# AutoTunerV2.net
KiCad netlist of a schematic drawn in EAGLE
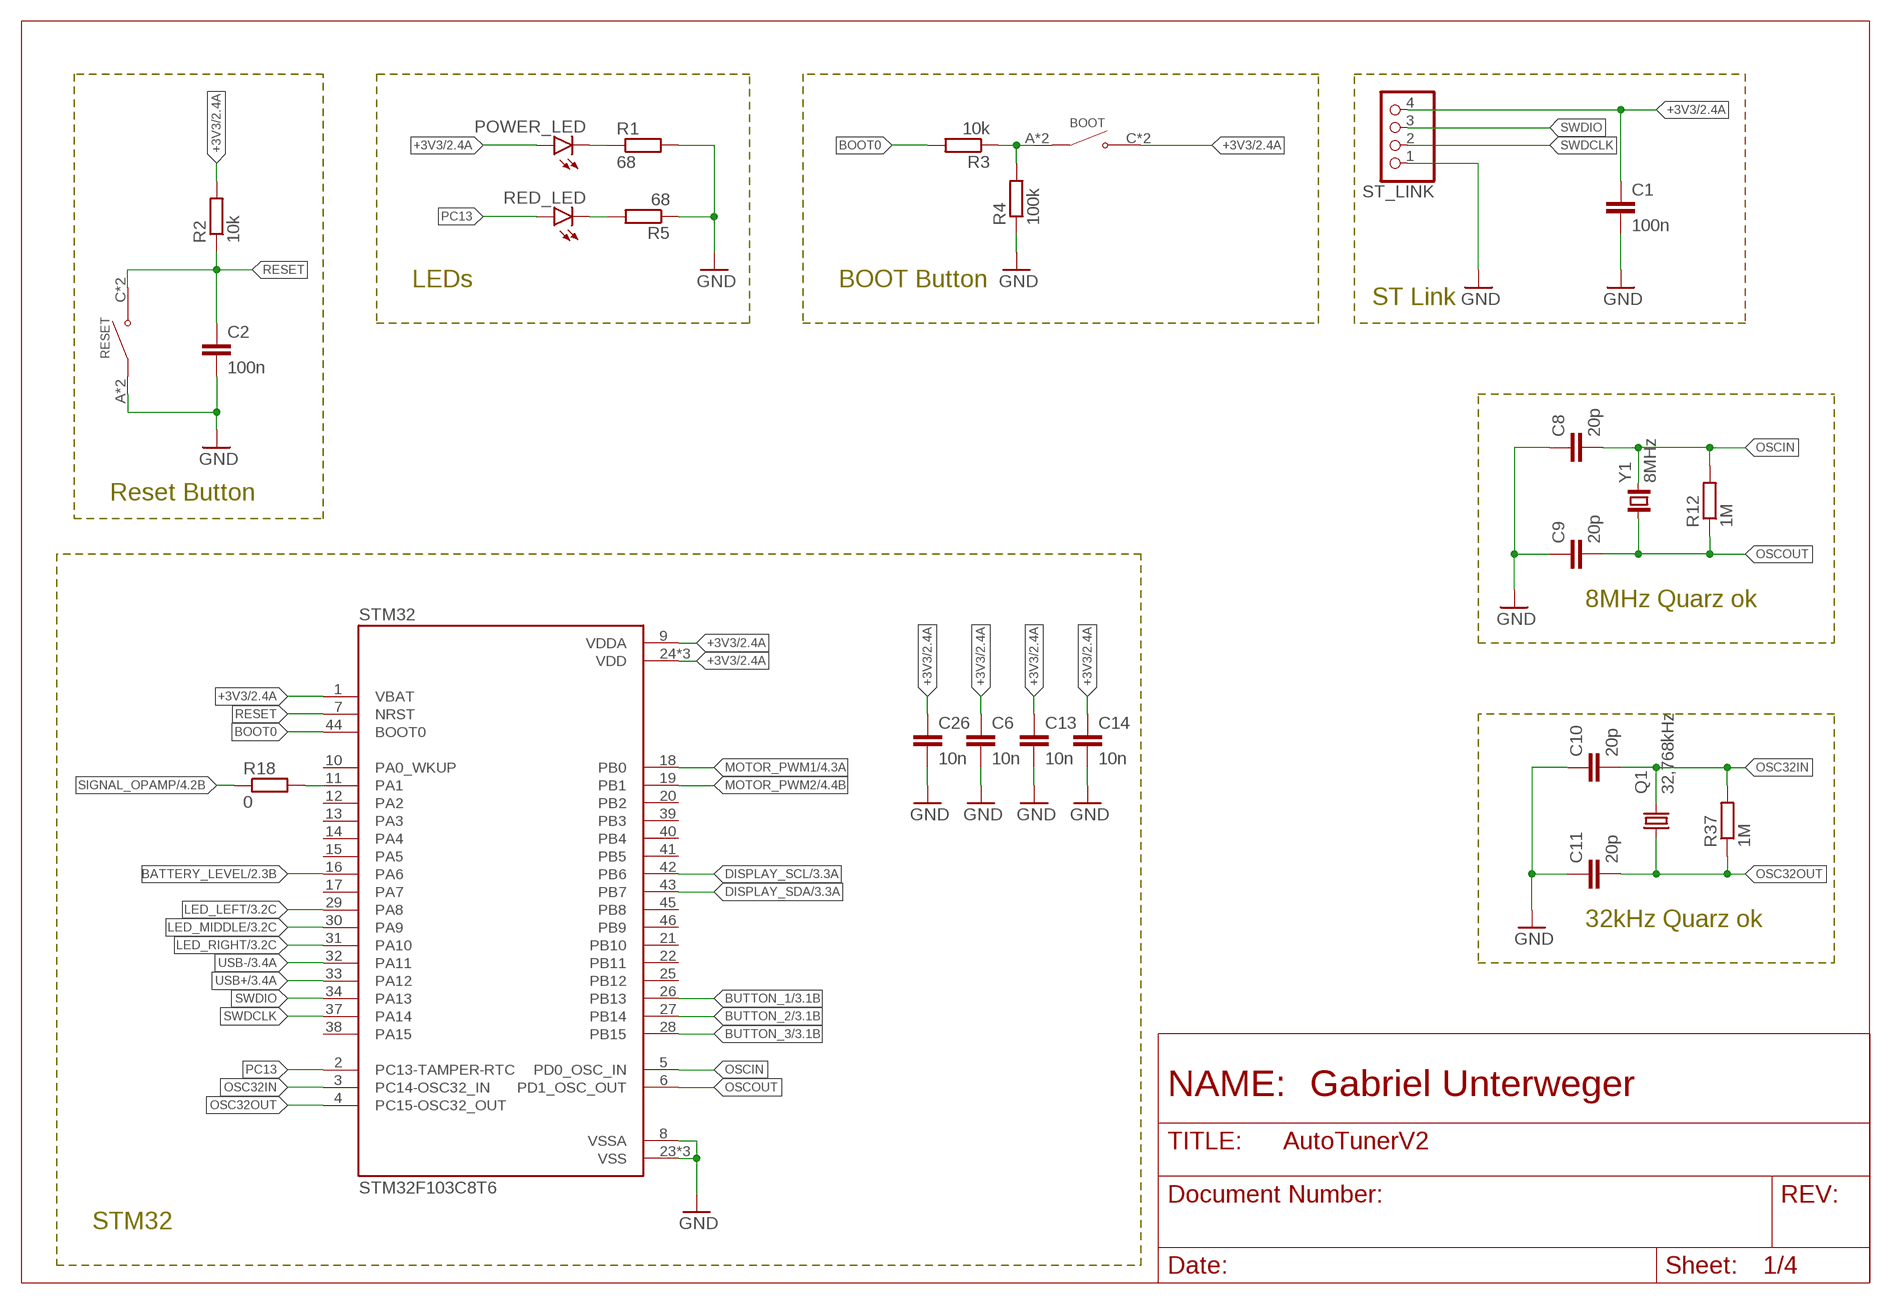
[diagram p0: schematic, sheet 1]
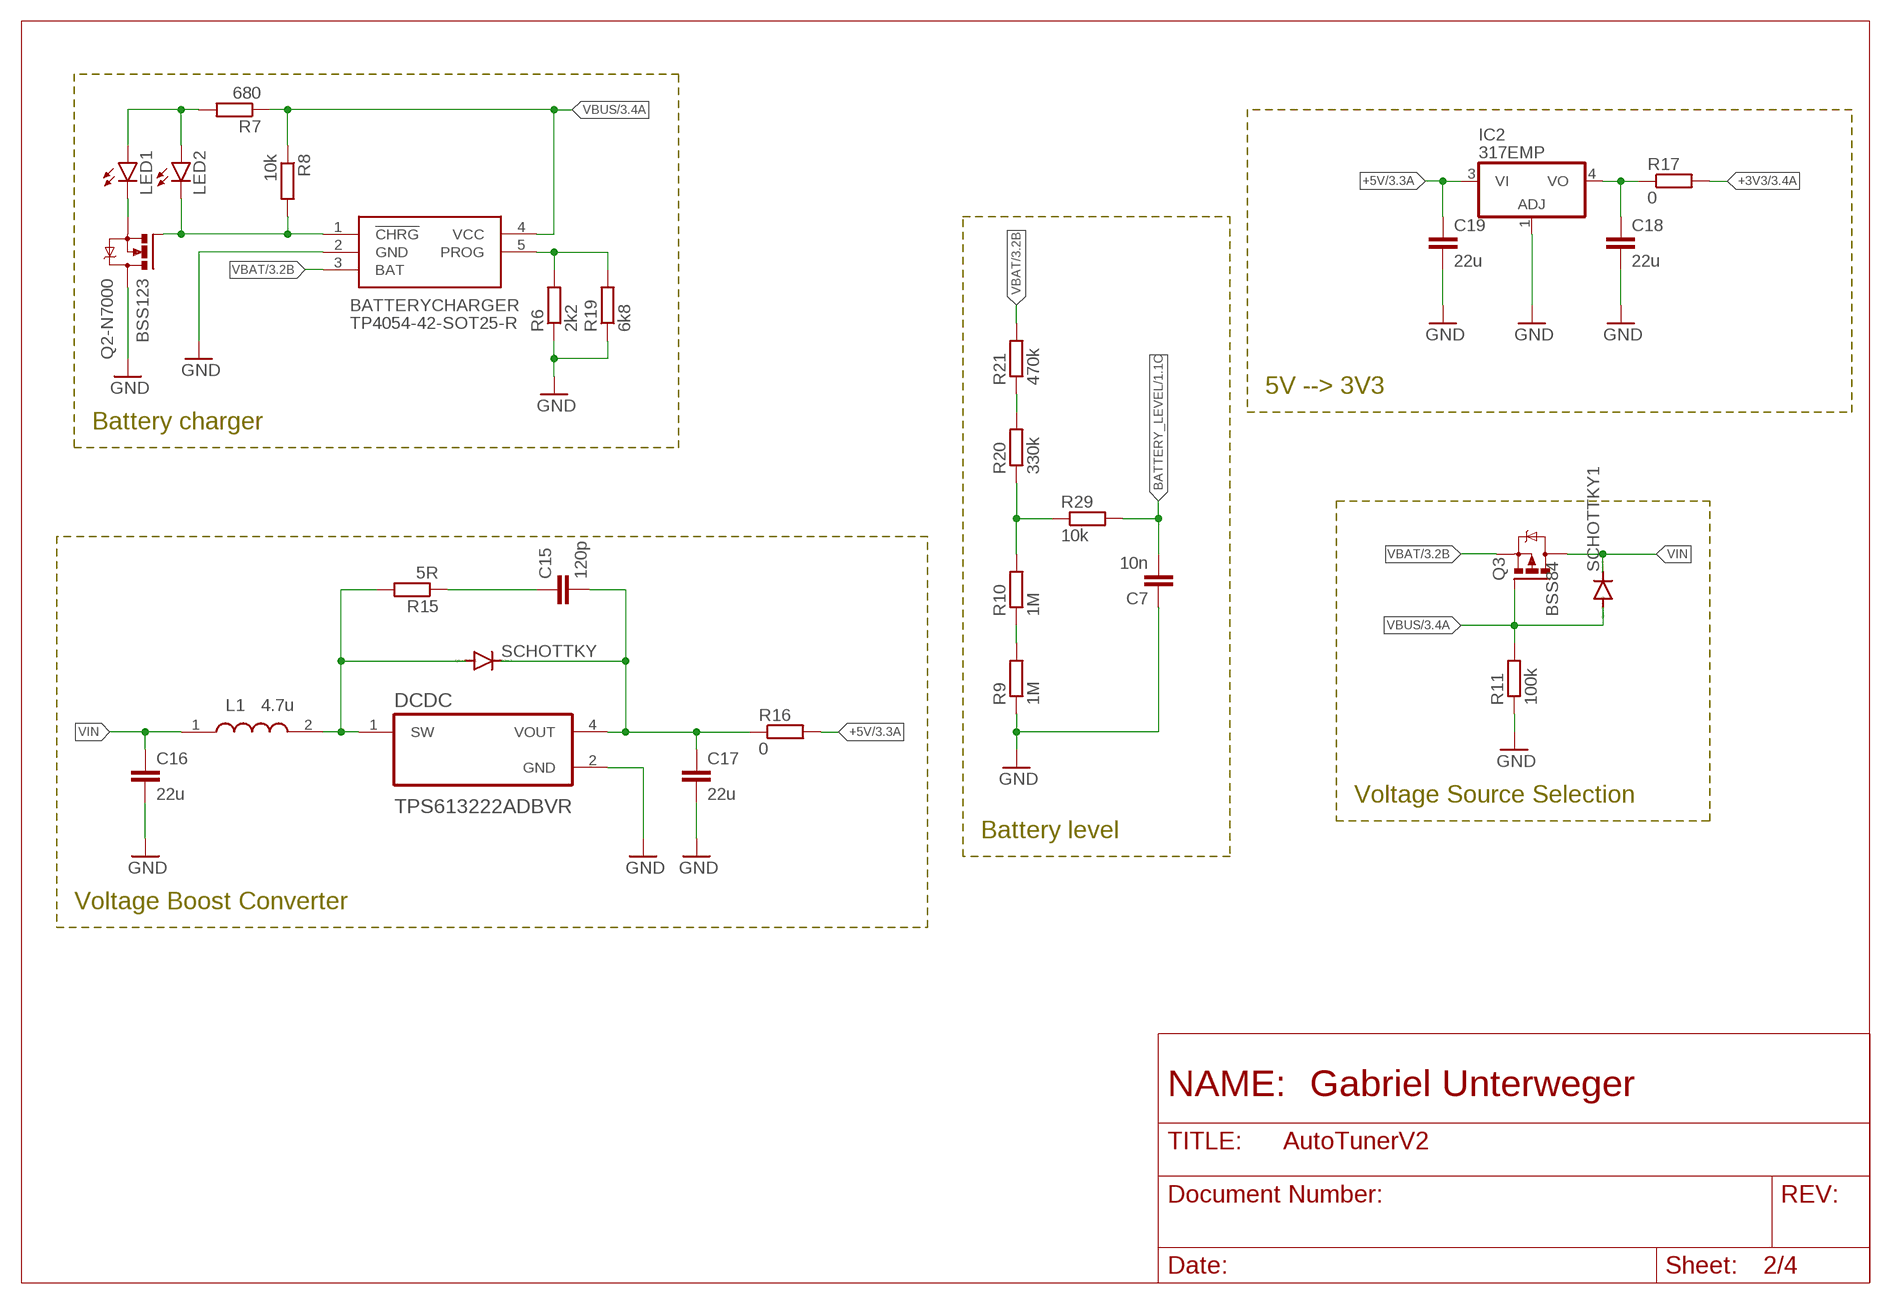
[diagram p1: schematic, sheet 2]
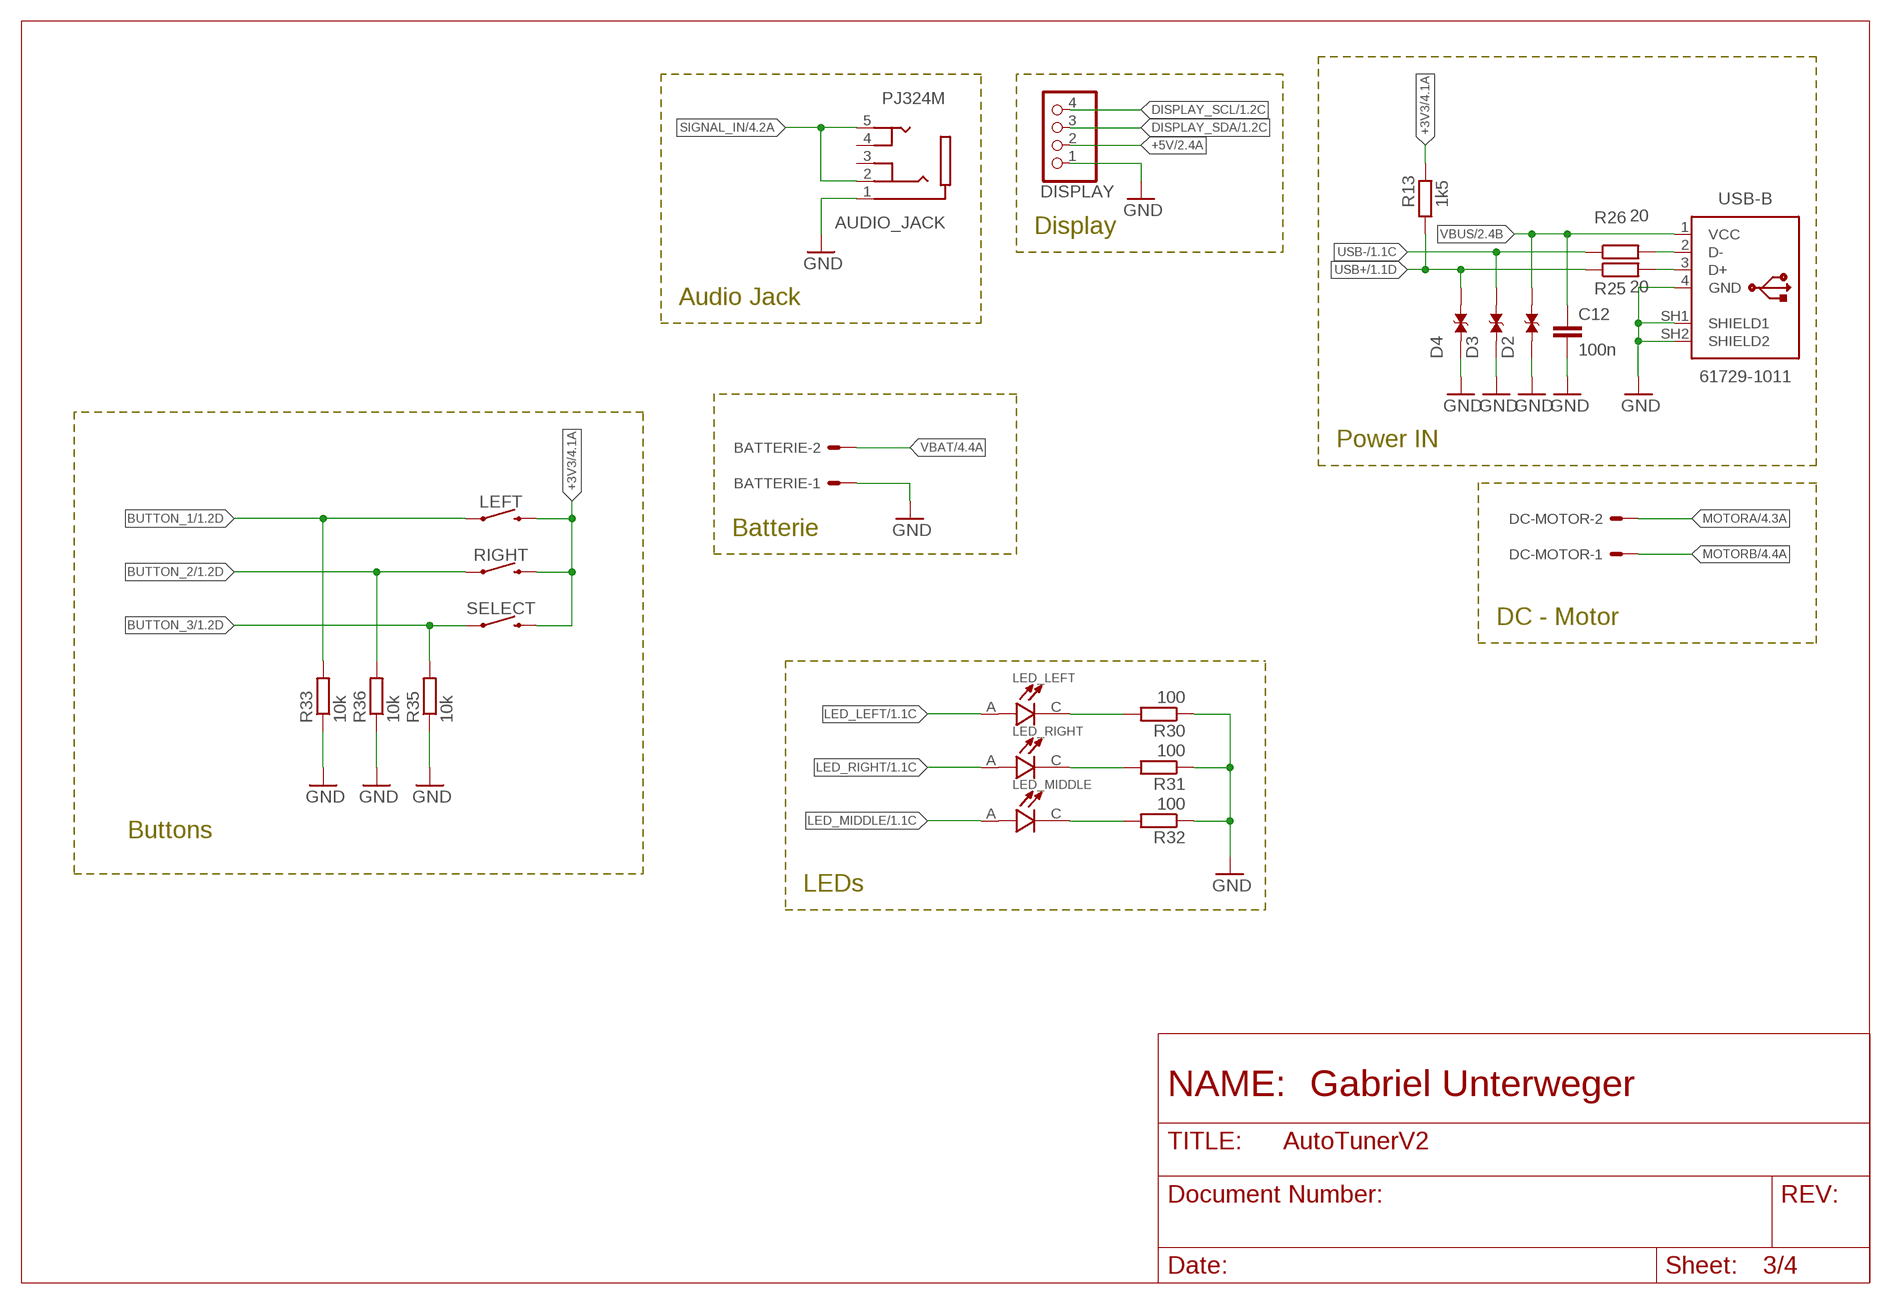
[diagram p2: schematic, sheet 3]
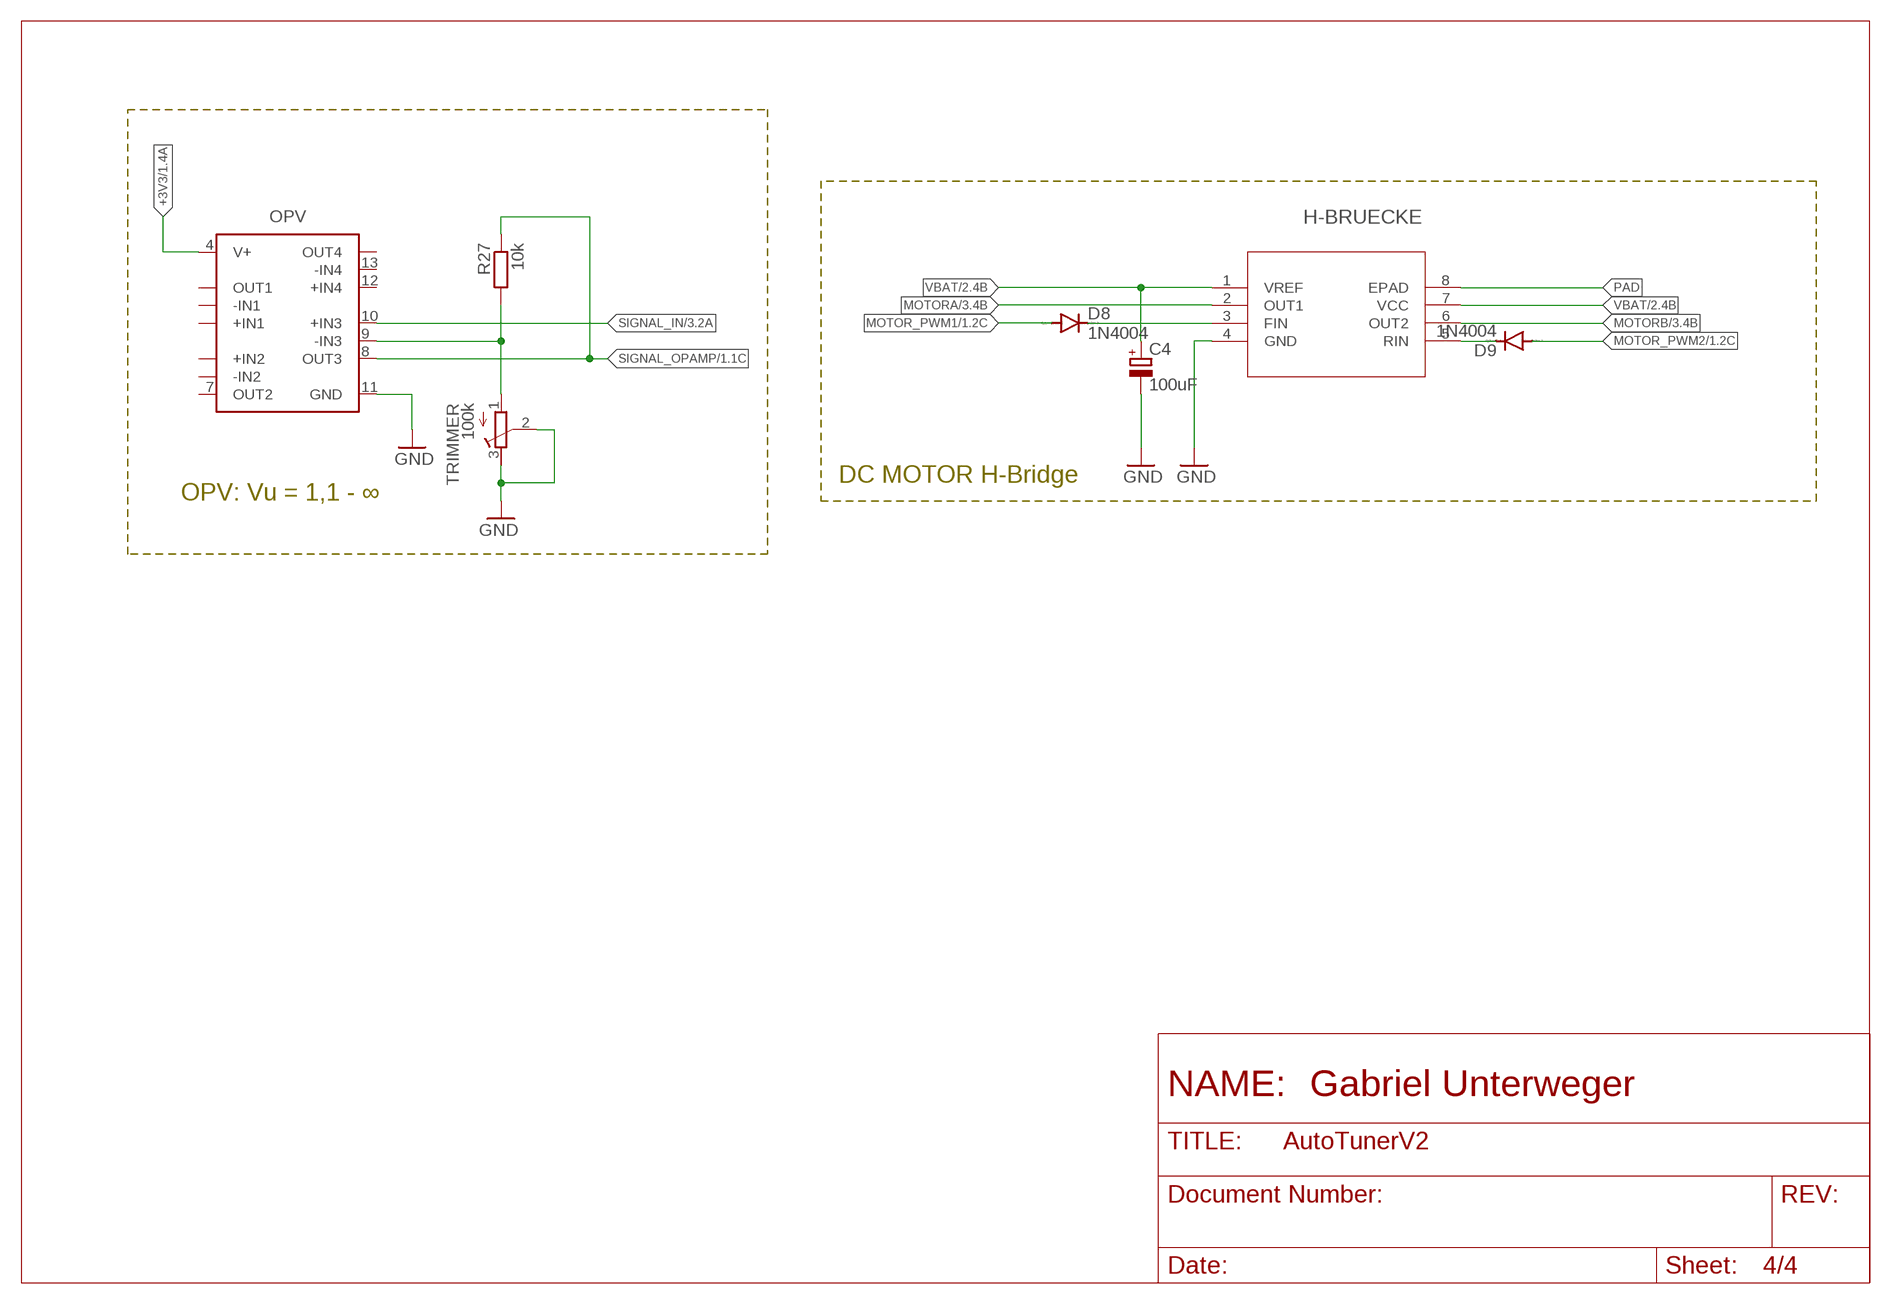
[diagram p3: schematic, sheet 4]

(export (version "E")
  (design (tool "Eeschema 10.0.6"))
  (components
    (comp (ref "BATTERYCHARGER")
      (value "TP4054-42-SOT25-R")
      (footprint "eagle-import:SOT95P280X100-5N")
      (fields (field (name "LCSC_PART") "C32574"))
      (libsource (lib "eagle-import") (part "TP4054-42-SOT25-R"))
    )
    (comp (ref "C7")
      (value "10n")
      (footprint "eagle-import:C0805")
      (libsource (lib "eagle-import") (part "C-EUC0805"))
    )
    (comp (ref "C15")
      (value "120p")
      (footprint "eagle-import:C0805")
      (libsource (lib "eagle-import") (part "C-EUC0805"))
    )
    (comp (ref "C16")
      (value "22u")
      (footprint "eagle-import:C1206")
      (fields (field (name "LCSC_PART") "C5672"))
      (libsource (lib "eagle-import") (part "C-EUC1206"))
    )
    (comp (ref "C17")
      (value "22u")
      (footprint "eagle-import:C1206")
      (fields (field (name "LCSC_PART") "C5672"))
      (libsource (lib "eagle-import") (part "C-EUC1206"))
    )
    (comp (ref "C18")
      (value "22u")
      (footprint "eagle-import:C1206")
      (fields (field (name "LCSC_PART") "C5672"))
      (libsource (lib "eagle-import") (part "C-EUC1206"))
    )
    (comp (ref "C19")
      (value "22u")
      (footprint "eagle-import:C1206")
      (fields (field (name "LCSC_PART") "C5672"))
      (libsource (lib "eagle-import") (part "C-EUC1206"))
    )
    (comp (ref "DCDC")
      (value "TPS613222ADBVR")
      (footprint "eagle-import:SOT95P280X145-5N")
      (fields (field (name "MF") "Texas Instruments") (field (name "LCSC_PART") "C2071163"))
      (libsource (lib "eagle-import") (part "TPS613222ADBVR"))
    )
    (comp (ref "IC2")
      (value "317EMP")
      (footprint "eagle-import:SOT223")
      (fields (field (name "LCSC_PART") "C6186"))
      (libsource (lib "eagle-import") (part "317EMP"))
    )
    (comp (ref "L1")
      (value "4.7u")
      (footprint "eagle-import:DFE2HCAH1R0MJ0L")
      (fields
        (field (name "ARROW_PART_NUMBER") "DFE252012P-4R7M=P2")
        (field (name "MOUSER_PART_NUMBER") "81-DFE252012P-4R7MP2")
        (field (name "LCSC_PART") "C3093670")
      )
      (libsource (lib "eagle-import") (part "DFE252012P-4R7M=P2"))
    )
    (comp (ref "LED1")
      (value "LEDCHIPLED_0805")
      (footprint "eagle-import:CHIPLED_0805")
      (fields (field (name "LCSC_PART") "C2297"))
      (libsource (lib "eagle-import") (part "LEDCHIPLED_0805"))
    )
    (comp (ref "LED2")
      (value "LEDCHIPLED_0805")
      (footprint "eagle-import:CHIPLED_0805")
      (fields (field (name "LCSC_PART") "C84256"))
      (libsource (lib "eagle-import") (part "LEDCHIPLED_0805"))
    )
    (comp (ref "Q2-N7000")
      (value "BSS123")
      (footprint "eagle-import:SOT23")
      (fields
        (field (name "MANUFACTURER") "ON Semiconductor")
        (field (name "MPN") "BSS123L")
        (field (name "LCSC_PART") "C20917")
      )
      (libsource (lib "eagle-import") (part "NMOSFET__SOT23-GSDBSS123"))
    )
    (comp (ref "Q3")
      (value "BSS84")
      (footprint "eagle-import:SOT23")
      (fields (field (name "MANUFACTURER") "ON Semiconductor"))
      (libsource (lib "eagle-import") (part "PMOSFET__SOT23-GSDBSS84"))
    )
    (comp (ref "R6")
      (value "2k2")
      (footprint "eagle-import:R0805")
      (libsource (lib "eagle-import") (part "R-EU_R0805"))
    )
    (comp (ref "R7")
      (value "680")
      (footprint "eagle-import:R0805")
      (libsource (lib "eagle-import") (part "R-EU_R0805"))
    )
    (comp (ref "R8")
      (value "10k")
      (footprint "eagle-import:R0805")
      (libsource (lib "eagle-import") (part "R-EU_R0805"))
    )
    (comp (ref "R9")
      (value "1M")
      (footprint "eagle-import:R0805")
      (libsource (lib "eagle-import") (part "R-EU_R0805"))
    )
    (comp (ref "R10")
      (value "1M")
      (footprint "eagle-import:R0805")
      (libsource (lib "eagle-import") (part "R-EU_R0805"))
    )
    (comp (ref "R11")
      (value "100k")
      (footprint "eagle-import:R0805")
      (libsource (lib "eagle-import") (part "R-EU_R0805"))
    )
    (comp (ref "R15")
      (value "5R")
      (footprint "eagle-import:R0805")
      (libsource (lib "eagle-import") (part "R-EU_R0805"))
    )
    (comp (ref "R16")
      (value "0")
      (footprint "eagle-import:R0805")
      (libsource (lib "eagle-import") (part "R-EU_R0805"))
    )
    (comp (ref "R17")
      (value "0")
      (footprint "eagle-import:R0805")
      (libsource (lib "eagle-import") (part "R-EU_R0805"))
    )
    (comp (ref "R19")
      (value "6k8")
      (footprint "eagle-import:R0805")
      (libsource (lib "eagle-import") (part "R-EU_R0805"))
    )
    (comp (ref "R20")
      (value "330k")
      (footprint "eagle-import:R0805")
      (libsource (lib "eagle-import") (part "R-EU_R0805"))
    )
    (comp (ref "R21")
      (value "470k")
      (footprint "eagle-import:R0805")
      (libsource (lib "eagle-import") (part "R-EU_R0805"))
    )
    (comp (ref "R29")
      (value "10k")
      (footprint "eagle-import:R0805")
      (libsource (lib "eagle-import") (part "R-EU_R0805"))
    )
    (comp (ref "SCHOTTKY")
      (value "DIODE-SOD323-R")
      (footprint "eagle-import:SOD323-R")
      (fields (field (name "LCSC_PART") "C191023"))
      (libsource (lib "eagle-import") (part "DIODE-SOD323-R"))
    )
    (comp (ref "SCHOTTKY1")
      (value "DIODE-SOD323-R")
      (footprint "eagle-import:SOD323-R")
      (fields (field (name "LCSC_PART") "C191023"))
      (libsource (lib "eagle-import") (part "DIODE-SOD323-R"))
    )
    (comp (ref "AUDIO_JACK")
      (value "PJ324M")
      (footprint "eagle-import:WENZHOU_PJ324M")
      (fields (field (name "MF") "Wenzhou QingPu Electronics Co.Ltd"))
      (libsource (lib "eagle-import") (part "PJ324M"))
    )
    (comp (ref "BATTERIE")
      (value "22-27-2021-02")
      (footprint "eagle-import:6410-02")
      (fields (field (name "MF") "MOLEX"))
      (libsource (lib "eagle-import") (part "22-?-0227-2021"))
    )
    (comp (ref "C12")
      (value "100n")
      (footprint "eagle-import:C0805")
      (libsource (lib "eagle-import") (part "C-EUC0805"))
    )
    (comp (ref "D2")
      (value "TESD5V0L1UC_RJG")
      (footprint "eagle-import:DIO_TESD5V0L1UC_RJG")
      (fields
        (field (name "MF") "Taiwan Semiconductor Corporation")
        (field (name "MP") "TESD5V0L1UC RJG")
        (field (name "LCSC_PART") "C7420372")
      )
      (libsource (lib "eagle-import") (part "TESD5V0L1UC_RJG"))
    )
    (comp (ref "D3")
      (value "TESD5V0L1UC_RJG")
      (footprint "eagle-import:DIO_TESD5V0L1UC_RJG")
      (fields
        (field (name "MF") "Taiwan Semiconductor Corporation")
        (field (name "MP") "TESD5V0L1UC RJG")
        (field (name "LCSC_PART") "C7420372")
      )
      (libsource (lib "eagle-import") (part "TESD5V0L1UC_RJG"))
    )
    (comp (ref "D4")
      (value "TESD5V0L1UC_RJG")
      (footprint "eagle-import:DIO_TESD5V0L1UC_RJG")
      (fields
        (field (name "MF") "Taiwan Semiconductor Corporation")
        (field (name "MP") "TESD5V0L1UC RJG")
        (field (name "LCSC_PART") "C7420372")
      )
      (libsource (lib "eagle-import") (part "TESD5V0L1UC_RJG"))
    )
    (comp (ref "DC-MOTOR")
      (value "22-27-2021-02")
      (footprint "eagle-import:6410-02")
      (fields (field (name "MF") "MOLEX"))
      (libsource (lib "eagle-import") (part "22-?-0227-2021"))
    )
    (comp (ref "DISPLAY")
      (value "PINHD-1X4")
      (footprint "eagle-import:1X04")
      (libsource (lib "eagle-import") (part "PINHD-1X4"))
    )
    (comp (ref "LED_LEFT")
      (value "L-53GD")
      (footprint "eagle-import:LEDRD254W50D500H1060")
      (fields (field (name "MF") "Kingbright"))
      (libsource (lib "eagle-import") (part "L-53GD"))
    )
    (comp (ref "LED_MIDDLE")
      (value "L-53GD")
      (footprint "eagle-import:LEDRD254W50D500H1060")
      (fields (field (name "MF") "Kingbright"))
      (libsource (lib "eagle-import") (part "L-53GD"))
    )
    (comp (ref "LED_RIGHT")
      (value "L-53GD")
      (footprint "eagle-import:LEDRD254W50D500H1060")
      (fields (field (name "MF") "Kingbright"))
      (libsource (lib "eagle-import") (part "L-53GD"))
    )
    (comp (ref "LEFT")
      (value "MOMENTARY-SWITCH-SPST-PTH-12MM")
      (footprint "eagle-import:TACTILE_SWITCH_PTH_12MM")
      (libsource (lib "eagle-import") (part "MOMENTARY-SWITCH-SPST-PTH-12MM"))
    )
    (comp (ref "R13")
      (value "1k5")
      (footprint "eagle-import:R0805")
      (libsource (lib "eagle-import") (part "R-EU_R0805"))
    )
    (comp (ref "R25")
      (value "20")
      (footprint "eagle-import:R0805")
      (libsource (lib "eagle-import") (part "R-EU_R0805"))
    )
    (comp (ref "R26")
      (value "20")
      (footprint "eagle-import:R0805")
      (libsource (lib "eagle-import") (part "R-EU_R0805"))
    )
    (comp (ref "R30")
      (value "100")
      (footprint "eagle-import:R0805")
      (libsource (lib "eagle-import") (part "R-EU_R0805"))
    )
    (comp (ref "R31")
      (value "100")
      (footprint "eagle-import:R0805")
      (libsource (lib "eagle-import") (part "R-EU_R0805"))
    )
    (comp (ref "R32")
      (value "100")
      (footprint "eagle-import:R0805")
      (libsource (lib "eagle-import") (part "R-EU_R0805"))
    )
    (comp (ref "R33")
      (value "10k")
      (footprint "eagle-import:R0805")
      (libsource (lib "eagle-import") (part "R-EU_R0805"))
    )
    (comp (ref "R35")
      (value "10k")
      (footprint "eagle-import:R0805")
      (libsource (lib "eagle-import") (part "R-EU_R0805"))
    )
    (comp (ref "R36")
      (value "10k")
      (footprint "eagle-import:R0805")
      (libsource (lib "eagle-import") (part "R-EU_R0805"))
    )
    (comp (ref "RIGHT")
      (value "MOMENTARY-SWITCH-SPST-PTH-12MM")
      (footprint "eagle-import:TACTILE_SWITCH_PTH_12MM")
      (libsource (lib "eagle-import") (part "MOMENTARY-SWITCH-SPST-PTH-12MM"))
    )
    (comp (ref "SELECT")
      (value "MOMENTARY-SWITCH-SPST-PTH-12MM")
      (footprint "eagle-import:TACTILE_SWITCH_PTH_12MM")
      (libsource (lib "eagle-import") (part "MOMENTARY-SWITCH-SPST-PTH-12MM"))
    )
    (comp (ref "USB-B")
      (value "61729-1011")
      (footprint "eagle-import:61729-1011BLF")
      (fields (field (name "MANUFACTURER") "Amphenol ICC (FCI)") (field (name "MPN") "61729-1011BLF"))
      (libsource (lib "eagle-import") (part "61729-1011"))
    )
    (comp (ref "C4")
      (value "100uF")
      (footprint "eagle-import:B45181A")
      (libsource (lib "eagle-import") (part "CPOL-EUB45181A"))
    )
    (comp (ref "D8")
      (value "1N4004")
      (footprint "eagle-import:DO41-10")
      (libsource (lib "eagle-import") (part "1N4004"))
    )
    (comp (ref "D9")
      (value "1N4004")
      (footprint "eagle-import:DO41-10")
      (libsource (lib "eagle-import") (part "1N4004"))
    )
    (comp (ref "H-BRUECKE")
      (value "BD6222HFP-TRHRP7_ROM-M")
      (footprint "eagle-import:HRP7_ROM-M")
      (fields
        (field (name "MANUFACTURER_PART_NUMBER") "BD6222HFP-TR")
        (field (name "COPYRIGHT") "Copyright (C) 2022 Ultra Librarian. All rights reserved.")
      )
      (libsource (lib "eagle-import") (part "BD6222HFP-TRHRP7_ROM-M"))
    )
    (comp (ref "OPV")
      (value "LM324_SOIC")
      (footprint "eagle-import:SOIC127P600X175-14N")
      (fields (field (name "MANUFACTURER") "Generic") (field (name "LCSC_PART") "C71035"))
      (libsource (lib "eagle-import") (part "LM324_SOIC"))
    )
    (comp (ref "R27")
      (value "10k")
      (footprint "eagle-import:R0805")
      (libsource (lib "eagle-import") (part "R-EU_R0805"))
    )
    (comp (ref "TRIMMER")
      (value "100k")
      (footprint "eagle-import:RTRIM64Y")
      (libsource (lib "eagle-import") (part "R-TRIMM64Y"))
    )
    (comp (ref "BOOT")
      (value "TS-1187A-B-A-B")
      (footprint "eagle-import:SW_TS-1187A-B-A-B")
      (fields (field (name "MF") "XKB Industrial Precision") (field (name "LCSC_PART") "C318884"))
      (libsource (lib "eagle-import") (part "TS-1187A-B-A-B"))
    )
    (comp (ref "C1")
      (value "100n")
      (footprint "eagle-import:C0805")
      (libsource (lib "eagle-import") (part "C-EUC0805"))
    )
    (comp (ref "C2")
      (value "100n")
      (footprint "eagle-import:C0805")
      (libsource (lib "eagle-import") (part "C-EUC0805"))
    )
    (comp (ref "C6")
      (value "10n")
      (footprint "eagle-import:C0805")
      (libsource (lib "eagle-import") (part "C-EUC0805"))
    )
    (comp (ref "C8")
      (value "20p")
      (footprint "eagle-import:C0805")
      (libsource (lib "eagle-import") (part "C-EUC0805"))
    )
    (comp (ref "C9")
      (value "20p")
      (footprint "eagle-import:C0805")
      (libsource (lib "eagle-import") (part "C-EUC0805"))
    )
    (comp (ref "C10")
      (value "20p")
      (footprint "eagle-import:C0805")
      (libsource (lib "eagle-import") (part "C-EUC0805"))
    )
    (comp (ref "C11")
      (value "20p")
      (footprint "eagle-import:C0805")
      (libsource (lib "eagle-import") (part "C-EUC0805"))
    )
    (comp (ref "C13")
      (value "10n")
      (footprint "eagle-import:C0805")
      (libsource (lib "eagle-import") (part "C-EUC0805"))
    )
    (comp (ref "C14")
      (value "10n")
      (footprint "eagle-import:C0805")
      (libsource (lib "eagle-import") (part "C-EUC0805"))
    )
    (comp (ref "C26")
      (value "10n")
      (footprint "eagle-import:C0805")
      (libsource (lib "eagle-import") (part "C-EUC0805"))
    )
    (comp (ref "POWER_LED")
      (value "LEDCHIPLED_0805")
      (footprint "eagle-import:CHIPLED_0805")
      (fields (field (name "LCSC_PART") "C2297"))
      (libsource (lib "eagle-import") (part "LEDCHIPLED_0805"))
    )
    (comp (ref "Q1")
      (value "32,768kHz")
      (footprint "eagle-import:3.2X1.5")
      (fields (field (name "LCSC_PART") "C32346"))
      (libsource (lib "eagle-import") (part "KX-327-NHF"))
    )
    (comp (ref "R1")
      (value "68")
      (footprint "eagle-import:R0805")
      (fields (field (name "LCSC_PART") "C17802"))
      (libsource (lib "eagle-import") (part "R-EU_R0805"))
    )
    (comp (ref "R2")
      (value "10k")
      (footprint "eagle-import:R0805")
      (libsource (lib "eagle-import") (part "R-EU_R0805"))
    )
    (comp (ref "R3")
      (value "10k")
      (footprint "eagle-import:R0805")
      (libsource (lib "eagle-import") (part "R-EU_R0805"))
    )
    (comp (ref "R4")
      (value "100k")
      (footprint "eagle-import:R0805")
      (libsource (lib "eagle-import") (part "R-EU_R0805"))
    )
    (comp (ref "R5")
      (value "68")
      (footprint "eagle-import:R0805")
      (fields (field (name "LCSC_PART") "C17802"))
      (libsource (lib "eagle-import") (part "R-EU_R0805"))
    )
    (comp (ref "R12")
      (value "1M")
      (footprint "eagle-import:R0805")
      (libsource (lib "eagle-import") (part "R-EU_R0805"))
    )
    (comp (ref "R18")
      (value "0")
      (footprint "eagle-import:R0805")
      (libsource (lib "eagle-import") (part "R-EU_R0805"))
    )
    (comp (ref "R37")
      (value "1M")
      (footprint "eagle-import:R0805")
      (libsource (lib "eagle-import") (part "R-EU_R0805"))
    )
    (comp (ref "RED_LED")
      (value "LEDCHIPLED_0805")
      (footprint "eagle-import:CHIPLED_0805")
      (fields (field (name "LCSC_PART") "C84256"))
      (libsource (lib "eagle-import") (part "LEDCHIPLED_0805"))
    )
    (comp (ref "RESET")
      (value "TS-1187A-B-A-B")
      (footprint "eagle-import:SW_TS-1187A-B-A-B")
      (fields (field (name "MF") "XKB Industrial Precision") (field (name "LCSC_PART") "C318884"))
      (libsource (lib "eagle-import") (part "TS-1187A-B-A-B"))
    )
    (comp (ref "STM32")
      (value "STM32F103C8T6")
      (footprint "eagle-import:QFP50P900X900X160-48N")
      (fields (field (name "MF") "STMicroelectronics") (field (name "LCSC_PART") "C8734"))
      (libsource (lib "eagle-import") (part "STM32F103C8T6"))
    )
    (comp (ref "ST_LINK")
      (value "PINHD-1X4")
      (footprint "eagle-import:1X04")
      (libsource (lib "eagle-import") (part "PINHD-1X4"))
    )
    (comp (ref "Y1")
      (value "8MHz")
      (footprint "eagle-import:CRYSTAL_2-SMD-5X3")
      (fields (field (name "LCSC_PART") "C115962"))
      (libsource (lib "eagle-import") (part "CRYSTAL_NX5032GA"))
    )
  )
  (nets
    (net (code "1") (name "+3V3") (class "Default")
      (node (ref "BOOT") (pin "C") (pinfunction "NO_C") (pintype "passive"))
      (node (ref "BOOT") (pin "D") (pinfunction "NO_D") (pintype "passive"))
      (node (ref "C1") (pin "1") (pinfunction "1_1") (pintype "passive"))
      (node (ref "C13") (pin "1") (pinfunction "1_1") (pintype "passive"))
      (node (ref "C14") (pin "1") (pinfunction "1_1") (pintype "passive"))
      (node (ref "C26") (pin "1") (pinfunction "1_1") (pintype "passive"))
      (node (ref "C6") (pin "1") (pinfunction "1_1") (pintype "passive"))
      (node (ref "LEFT") (pin "3") (pinfunction "2_3") (pintype "passive"))
      (node (ref "OPV") (pin "4") (pinfunction "V+_4") (pintype "passive"))
      (node (ref "POWER_LED") (pin "A") (pinfunction "A_A") (pintype "passive"))
      (node (ref "R13") (pin "2") (pinfunction "2_2") (pintype "passive"))
      (node (ref "R17") (pin "2") (pinfunction "2_2") (pintype "passive"))
      (node (ref "R2") (pin "2") (pinfunction "2_2") (pintype "passive"))
      (node (ref "RIGHT") (pin "3") (pinfunction "2_3") (pintype "passive"))
      (node (ref "SELECT") (pin "3") (pinfunction "2_3") (pintype "passive"))
      (node (ref "STM32") (pin "1") (pinfunction "VBAT_1") (pintype "bidirectional"))
      (node (ref "STM32") (pin "24") (pinfunction "VDD_24") (pintype "power_in"))
      (node (ref "STM32") (pin "36") (pinfunction "VDD_36") (pintype "power_in"))
      (node (ref "STM32") (pin "48") (pinfunction "VDD_48") (pintype "power_in"))
      (node (ref "STM32") (pin "9") (pinfunction "VDDA_9") (pintype "power_in"))
      (node (ref "ST_LINK") (pin "4") (pinfunction "4_4") (pintype "passive"))
    )
    (net (code "2") (name "+5V") (class "Default")
      (node (ref "C19") (pin "1") (pinfunction "1_1") (pintype "passive"))
      (node (ref "DISPLAY") (pin "2") (pinfunction "2_2") (pintype "passive"))
      (node (ref "IC2") (pin "3") (pinfunction "VI_3") (pintype "input"))
      (node (ref "R16") (pin "2") (pinfunction "2_2") (pintype "passive"))
    )
    (net (code "3") (name "BATTERY_LEVEL") (class "Default")
      (node (ref "C7") (pin "2") (pinfunction "2_2") (pintype "passive"))
      (node (ref "R29") (pin "2") (pinfunction "2_2") (pintype "passive"))
      (node (ref "STM32") (pin "16") (pinfunction "PA6_16") (pintype "bidirectional"))
    )
    (net (code "4") (name "BOOT0") (class "Default")
      (node (ref "R3") (pin "2") (pinfunction "2_2") (pintype "passive"))
      (node (ref "STM32") (pin "44") (pinfunction "BOOT0_44") (pintype "input"))
    )
    (net (code "5") (name "BUTTON_1") (class "Default")
      (node (ref "LEFT") (pin "1") (pinfunction "1_1") (pintype "passive"))
      (node (ref "R33") (pin "2") (pinfunction "2_2") (pintype "passive"))
      (node (ref "STM32") (pin "26") (pinfunction "PB13_26") (pintype "bidirectional"))
    )
    (net (code "6") (name "BUTTON_2") (class "Default")
      (node (ref "R36") (pin "2") (pinfunction "2_2") (pintype "passive"))
      (node (ref "RIGHT") (pin "1") (pinfunction "1_1") (pintype "passive"))
      (node (ref "STM32") (pin "27") (pinfunction "PB14_27") (pintype "bidirectional"))
    )
    (net (code "7") (name "BUTTON_3") (class "Default")
      (node (ref "R35") (pin "2") (pinfunction "2_2") (pintype "passive"))
      (node (ref "SELECT") (pin "1") (pinfunction "1_1") (pintype "passive"))
      (node (ref "STM32") (pin "28") (pinfunction "PB15_28") (pintype "bidirectional"))
    )
    (net (code "8") (name "DISPLAY_SCL") (class "Default")
      (node (ref "DISPLAY") (pin "4") (pinfunction "4_4") (pintype "passive"))
      (node (ref "STM32") (pin "42") (pinfunction "PB6_42") (pintype "bidirectional"))
    )
    (net (code "9") (name "DISPLAY_SDA") (class "Default")
      (node (ref "DISPLAY") (pin "3") (pinfunction "3_3") (pintype "passive"))
      (node (ref "STM32") (pin "43") (pinfunction "PB7_43") (pintype "bidirectional"))
    )
    (net (code "10") (name "GND") (class "Default")
      (node (ref "AUDIO_JACK") (pin "1") (pinfunction "SLEEVE_1") (pintype "passive"))
      (node (ref "BATTERIE") (pin "1") (pinfunction "S_1") (pintype "passive"))
      (node (ref "BATTERYCHARGER") (pin "2") (pinfunction "GND_2") (pintype "bidirectional"))
      (node (ref "C1") (pin "2") (pinfunction "2_2") (pintype "passive"))
      (node (ref "C10") (pin "1") (pinfunction "1_1") (pintype "passive"))
      (node (ref "C11") (pin "1") (pinfunction "1_1") (pintype "passive"))
      (node (ref "C12") (pin "2") (pinfunction "2_2") (pintype "passive"))
      (node (ref "C13") (pin "2") (pinfunction "2_2") (pintype "passive"))
      (node (ref "C14") (pin "2") (pinfunction "2_2") (pintype "passive"))
      (node (ref "C16") (pin "2") (pinfunction "2_2") (pintype "passive"))
      (node (ref "C17") (pin "2") (pinfunction "2_2") (pintype "passive"))
      (node (ref "C18") (pin "2") (pinfunction "2_2") (pintype "passive"))
      (node (ref "C19") (pin "2") (pinfunction "2_2") (pintype "passive"))
      (node (ref "C2") (pin "2") (pinfunction "2_2") (pintype "passive"))
      (node (ref "C26") (pin "2") (pinfunction "2_2") (pintype "passive"))
      (node (ref "C4") (pin "-") (pinfunction "-_-") (pintype "passive"))
      (node (ref "C6") (pin "2") (pinfunction "2_2") (pintype "passive"))
      (node (ref "C7") (pin "1") (pinfunction "1_1") (pintype "passive"))
      (node (ref "C8") (pin "1") (pinfunction "1_1") (pintype "passive"))
      (node (ref "C9") (pin "1") (pinfunction "1_1") (pintype "passive"))
      (node (ref "D2") (pin "1") (pinfunction "1_1") (pintype "passive"))
      (node (ref "D3") (pin "1") (pinfunction "1_1") (pintype "passive"))
      (node (ref "D4") (pin "1") (pinfunction "1_1") (pintype "passive"))
      (node (ref "DCDC") (pin "2") (pinfunction "GND_2") (pintype "power_in"))
      (node (ref "DISPLAY") (pin "1") (pinfunction "1_1") (pintype "passive"))
      (node (ref "H-BRUECKE") (pin "4") (pinfunction "GND_4") (pintype "passive"))
      (node (ref "IC2") (pin "1") (pinfunction "ADJ_1") (pintype "input"))
      (node (ref "OPV") (pin "11") (pinfunction "GND_11") (pintype "passive"))
      (node (ref "Q2-N7000") (pin "3") (pinfunction "D_3") (pintype "passive"))
      (node (ref "R1") (pin "2") (pinfunction "2_2") (pintype "passive"))
      (node (ref "R11") (pin "1") (pinfunction "1_1") (pintype "passive"))
      (node (ref "R19") (pin "1") (pinfunction "1_1") (pintype "passive"))
      (node (ref "R30") (pin "1") (pinfunction "1_1") (pintype "passive"))
      (node (ref "R31") (pin "1") (pinfunction "1_1") (pintype "passive"))
      (node (ref "R32") (pin "1") (pinfunction "1_1") (pintype "passive"))
      (node (ref "R33") (pin "1") (pinfunction "1_1") (pintype "passive"))
      (node (ref "R35") (pin "1") (pinfunction "1_1") (pintype "passive"))
      (node (ref "R36") (pin "1") (pinfunction "1_1") (pintype "passive"))
      (node (ref "R4") (pin "1") (pinfunction "1_1") (pintype "passive"))
      (node (ref "R5") (pin "1") (pinfunction "1_1") (pintype "passive"))
      (node (ref "R6") (pin "1") (pinfunction "1_1") (pintype "passive"))
      (node (ref "R9") (pin "1") (pinfunction "1_1") (pintype "passive"))
      (node (ref "RESET") (pin "A") (pinfunction "COM_A") (pintype "passive"))
      (node (ref "RESET") (pin "B") (pinfunction "COM_B") (pintype "passive"))
      (node (ref "STM32") (pin "23") (pinfunction "VSS_23") (pintype "power_in"))
      (node (ref "STM32") (pin "35") (pinfunction "VSS_35") (pintype "power_in"))
      (node (ref "STM32") (pin "47") (pinfunction "VSS_47") (pintype "power_in"))
      (node (ref "STM32") (pin "8") (pinfunction "VSSA_8") (pintype "power_in"))
      (node (ref "ST_LINK") (pin "1") (pinfunction "1_1") (pintype "passive"))
      (node (ref "TRIMMER") (pin "2") (pinfunction "S_2") (pintype "passive"))
      (node (ref "TRIMMER") (pin "3") (pinfunction "E_3") (pintype "passive"))
      (node (ref "USB-B") (pin "4") (pinfunction "GND_4") (pintype "power_in"))
      (node (ref "USB-B") (pin "SH1") (pinfunction "SHIELD1_SH1") (pintype "power_in"))
      (node (ref "USB-B") (pin "SH2") (pinfunction "SHIELD2_SH2") (pintype "power_in"))
    )
    (net (code "11") (name "LED_LEFT") (class "Default")
      (node (ref "LED_LEFT") (pin "A") (pinfunction "A_A") (pintype "passive"))
      (node (ref "STM32") (pin "29") (pinfunction "PA8_29") (pintype "bidirectional"))
    )
    (net (code "12") (name "LED_MIDDLE") (class "Default")
      (node (ref "LED_MIDDLE") (pin "A") (pinfunction "A_A") (pintype "passive"))
      (node (ref "STM32") (pin "30") (pinfunction "PA9_30") (pintype "bidirectional"))
    )
    (net (code "13") (name "LED_RIGHT") (class "Default")
      (node (ref "LED_RIGHT") (pin "A") (pinfunction "A_A") (pintype "passive"))
      (node (ref "STM32") (pin "31") (pinfunction "PA10_31") (pintype "bidirectional"))
    )
    (net (code "14") (name "MOTORA") (class "Default")
      (node (ref "DC-MOTOR") (pin "2") (pinfunction "S_2") (pintype "passive"))
      (node (ref "H-BRUECKE") (pin "2") (pinfunction "OUT1_2") (pintype "output"))
    )
    (net (code "15") (name "MOTORB") (class "Default")
      (node (ref "DC-MOTOR") (pin "1") (pinfunction "S_1") (pintype "passive"))
      (node (ref "H-BRUECKE") (pin "6") (pinfunction "OUT2_6") (pintype "output"))
    )
    (net (code "16") (name "MOTOR_PWM1") (class "Default")
      (node (ref "D8") (pin "A") (pinfunction "A_A") (pintype "passive"))
      (node (ref "STM32") (pin "18") (pinfunction "PB0_18") (pintype "bidirectional"))
    )
    (net (code "17") (name "MOTOR_PWM2") (class "Default")
      (node (ref "D9") (pin "A") (pinfunction "A_A") (pintype "passive"))
      (node (ref "STM32") (pin "19") (pinfunction "PB1_19") (pintype "bidirectional"))
    )
    (net (code "18") (name "Net-(BATTERYCHARGER-PROG)") (class "Default")
      (node (ref "BATTERYCHARGER") (pin "5") (pinfunction "PROG_5") (pintype "bidirectional"))
      (node (ref "R19") (pin "2") (pinfunction "2_2") (pintype "passive"))
      (node (ref "R6") (pin "2") (pinfunction "2_2") (pintype "passive"))
    )
    (net (code "19") (name "Net-(BATTERYCHARGER-~{CHRG})") (class "Default")
      (node (ref "BATTERYCHARGER") (pin "1") (pinfunction "~{CHRG}_1") (pintype "bidirectional"))
      (node (ref "LED2") (pin "C") (pinfunction "C_C") (pintype "passive"))
      (node (ref "Q2-N7000") (pin "1") (pinfunction "G_1") (pintype "passive"))
      (node (ref "R8") (pin "2") (pinfunction "2_2") (pintype "passive"))
    )
    (net (code "20") (name "Net-(BOOT-COM-PadA)") (class "Default")
      (node (ref "BOOT") (pin "A") (pinfunction "COM_A") (pintype "passive"))
      (node (ref "BOOT") (pin "B") (pinfunction "COM_B") (pintype "passive"))
      (node (ref "R3") (pin "1") (pinfunction "1_1") (pintype "passive"))
      (node (ref "R4") (pin "2") (pinfunction "2_2") (pintype "passive"))
    )
    (net (code "21") (name "Net-(C15-Pad1)") (class "Default")
      (node (ref "C15") (pin "1") (pinfunction "1_1") (pintype "passive"))
      (node (ref "R15") (pin "1") (pinfunction "1_1") (pintype "passive"))
    )
    (net (code "22") (name "Net-(DCDC-SW)") (class "Default")
      (node (ref "DCDC") (pin "1") (pinfunction "SW_1") (pintype "input"))
      (node (ref "L1") (pin "2") (pinfunction "2_2") (pintype "bidirectional"))
      (node (ref "R15") (pin "2") (pinfunction "2_2") (pintype "passive"))
      (node (ref "SCHOTTKY") (pin "A") (pinfunction "A_A") (pintype "passive"))
    )
    (net (code "23") (name "Net-(DCDC-VOUT)") (class "Default")
      (node (ref "C15") (pin "2") (pinfunction "2_2") (pintype "passive"))
      (node (ref "C17") (pin "1") (pinfunction "1_1") (pintype "passive"))
      (node (ref "DCDC") (pin "4") (pinfunction "VOUT_4") (pintype "output"))
      (node (ref "R16") (pin "1") (pinfunction "1_1") (pintype "passive"))
      (node (ref "SCHOTTKY") (pin "C") (pinfunction "C_C") (pintype "passive"))
    )
    (net (code "24") (name "Net-(H-BRUECKE-FIN)") (class "Default")
      (node (ref "D8") (pin "C") (pinfunction "C_C") (pintype "passive"))
      (node (ref "H-BRUECKE") (pin "3") (pinfunction "FIN_3") (pintype "passive"))
    )
    (net (code "25") (name "Net-(H-BRUECKE-RIN)") (class "Default")
      (node (ref "D9") (pin "C") (pinfunction "C_C") (pintype "passive"))
      (node (ref "H-BRUECKE") (pin "5") (pinfunction "RIN_5") (pintype "passive"))
    )
    (net (code "26") (name "Net-(IC2-VO)") (class "Default")
      (node (ref "C18") (pin "1") (pinfunction "1_1") (pintype "passive"))
      (node (ref "IC2") (pin "4") (pinfunction "VO_4") (pintype "passive"))
      (node (ref "R17") (pin "1") (pinfunction "1_1") (pintype "passive"))
    )
    (net (code "27") (name "Net-(LED1-PadA)") (class "Default")
      (node (ref "LED1") (pin "A") (pinfunction "A_A") (pintype "passive"))
      (node (ref "LED2") (pin "A") (pinfunction "A_A") (pintype "passive"))
      (node (ref "R7") (pin "2") (pinfunction "2_2") (pintype "passive"))
    )
    (net (code "28") (name "Net-(LED_LEFT-PadC)") (class "Default")
      (node (ref "LED_LEFT") (pin "C") (pinfunction "C_C") (pintype "passive"))
      (node (ref "R30") (pin "2") (pinfunction "2_2") (pintype "passive"))
    )
    (net (code "29") (name "Net-(LED_MIDDLE-PadC)") (class "Default")
      (node (ref "LED_MIDDLE") (pin "C") (pinfunction "C_C") (pintype "passive"))
      (node (ref "R32") (pin "2") (pinfunction "2_2") (pintype "passive"))
    )
    (net (code "30") (name "Net-(LED_RIGHT-PadC)") (class "Default")
      (node (ref "LED_RIGHT") (pin "C") (pinfunction "C_C") (pintype "passive"))
      (node (ref "R31") (pin "2") (pinfunction "2_2") (pintype "passive"))
    )
    (net (code "31") (name "Net-(OPV--IN3)") (class "Default")
      (node (ref "OPV") (pin "9") (pinfunction "-IN3_9") (pintype "passive"))
      (node (ref "R27") (pin "2") (pinfunction "2_2") (pintype "passive"))
      (node (ref "TRIMMER") (pin "1") (pinfunction "A_1") (pintype "passive"))
    )
    (net (code "32") (name "Net-(POWER_LED-PadC)") (class "Default")
      (node (ref "POWER_LED") (pin "C") (pinfunction "C_C") (pintype "passive"))
      (node (ref "R1") (pin "1") (pinfunction "1_1") (pintype "passive"))
    )
    (net (code "33") (name "Net-(Q2-N7000-S)") (class "Default")
      (node (ref "LED1") (pin "C") (pinfunction "C_C") (pintype "passive"))
      (node (ref "Q2-N7000") (pin "2") (pinfunction "S_2") (pintype "passive"))
    )
    (net (code "34") (name "Net-(R5-Pad2)") (class "Default")
      (node (ref "R5") (pin "2") (pinfunction "2_2") (pintype "passive"))
      (node (ref "RED_LED") (pin "C") (pinfunction "C_C") (pintype "passive"))
    )
    (net (code "35") (name "Net-(R10-Pad1)") (class "Default")
      (node (ref "R10") (pin "1") (pinfunction "1_1") (pintype "passive"))
      (node (ref "R9") (pin "2") (pinfunction "2_2") (pintype "passive"))
    )
    (net (code "36") (name "Net-(R10-Pad2)") (class "Default")
      (node (ref "R10") (pin "2") (pinfunction "2_2") (pintype "passive"))
      (node (ref "R20") (pin "1") (pinfunction "1_1") (pintype "passive"))
      (node (ref "R29") (pin "1") (pinfunction "1_1") (pintype "passive"))
    )
    (net (code "37") (name "Net-(R20-Pad2)") (class "Default")
      (node (ref "R20") (pin "2") (pinfunction "2_2") (pintype "passive"))
      (node (ref "R21") (pin "1") (pinfunction "1_1") (pintype "passive"))
    )
    (net (code "38") (name "Net-(STM32-PA1)") (class "Default")
      (node (ref "R18") (pin "2") (pinfunction "2_2") (pintype "passive"))
      (node (ref "STM32") (pin "11") (pinfunction "PA1_11") (pintype "bidirectional"))
    )
    (net (code "39") (name "Net-(USB-B-D+)") (class "Default")
      (node (ref "R25") (pin "2") (pinfunction "2_2") (pintype "passive"))
      (node (ref "USB-B") (pin "3") (pinfunction "D+_3") (pintype "bidirectional"))
    )
    (net (code "40") (name "Net-(USB-B-D-)") (class "Default")
      (node (ref "R26") (pin "2") (pinfunction "2_2") (pintype "passive"))
      (node (ref "USB-B") (pin "2") (pinfunction "D-_2") (pintype "bidirectional"))
    )
    (net (code "41") (name "OSC32IN") (class "Default")
      (node (ref "C10") (pin "2") (pinfunction "2_2") (pintype "passive"))
      (node (ref "Q1") (pin "2") (pinfunction "2_2") (pintype "passive"))
      (node (ref "R37") (pin "2") (pinfunction "2_2") (pintype "passive"))
      (node (ref "STM32") (pin "3") (pinfunction "PC14-OSC32_IN_3") (pintype "bidirectional"))
    )
    (net (code "42") (name "OSC32OUT") (class "Default")
      (node (ref "C11") (pin "2") (pinfunction "2_2") (pintype "passive"))
      (node (ref "Q1") (pin "1") (pinfunction "1_1") (pintype "passive"))
      (node (ref "R37") (pin "1") (pinfunction "1_1") (pintype "passive"))
      (node (ref "STM32") (pin "4") (pinfunction "PC15-OSC32_OUT_4") (pintype "bidirectional"))
    )
    (net (code "43") (name "OSCIN") (class "Default")
      (node (ref "C8") (pin "2") (pinfunction "2_2") (pintype "passive"))
      (node (ref "R12") (pin "2") (pinfunction "2_2") (pintype "passive"))
      (node (ref "STM32") (pin "5") (pinfunction "PD0_OSC_IN_5") (pintype "bidirectional"))
      (node (ref "Y1") (pin "2") (pinfunction "2_2") (pintype "passive"))
    )
    (net (code "44") (name "OSCOUT") (class "Default")
      (node (ref "C9") (pin "2") (pinfunction "2_2") (pintype "passive"))
      (node (ref "R12") (pin "1") (pinfunction "1_1") (pintype "passive"))
      (node (ref "STM32") (pin "6") (pinfunction "PD1_OSC_OUT_6") (pintype "bidirectional"))
      (node (ref "Y1") (pin "1") (pinfunction "1_1") (pintype "passive"))
    )
    (net (code "45") (name "PAD") (class "Default")
      (node (ref "H-BRUECKE") (pin "8") (pinfunction "EPAD_8") (pintype "passive"))
    )
    (net (code "46") (name "PC13") (class "Default")
      (node (ref "RED_LED") (pin "A") (pinfunction "A_A") (pintype "passive"))
      (node (ref "STM32") (pin "2") (pinfunction "PC13-TAMPER-RTC_2") (pintype "bidirectional"))
    )
    (net (code "47") (name "RESET") (class "Default")
      (node (ref "C2") (pin "1") (pinfunction "1_1") (pintype "passive"))
      (node (ref "R2") (pin "1") (pinfunction "1_1") (pintype "passive"))
      (node (ref "RESET") (pin "C") (pinfunction "NO_C") (pintype "passive"))
      (node (ref "RESET") (pin "D") (pinfunction "NO_D") (pintype "passive"))
      (node (ref "STM32") (pin "7") (pinfunction "NRST_7") (pintype "input"))
    )
    (net (code "48") (name "SIGNAL_IN") (class "Default")
      (node (ref "AUDIO_JACK") (pin "2") (pinfunction "RING_1_2") (pintype "passive"))
      (node (ref "AUDIO_JACK") (pin "5") (pinfunction "TIP_2_5") (pintype "passive"))
      (node (ref "OPV") (pin "10") (pinfunction "+IN3_10") (pintype "passive"))
    )
    (net (code "49") (name "SIGNAL_OPAMP") (class "Default")
      (node (ref "OPV") (pin "8") (pinfunction "OUT3_8") (pintype "passive"))
      (node (ref "R18") (pin "1") (pinfunction "1_1") (pintype "passive"))
      (node (ref "R27") (pin "1") (pinfunction "1_1") (pintype "passive"))
    )
    (net (code "50") (name "SWDCLK") (class "Default")
      (node (ref "STM32") (pin "37") (pinfunction "PA14_37") (pintype "bidirectional"))
      (node (ref "ST_LINK") (pin "2") (pinfunction "2_2") (pintype "passive"))
    )
    (net (code "51") (name "SWDIO") (class "Default")
      (node (ref "STM32") (pin "34") (pinfunction "PA13_34") (pintype "bidirectional"))
      (node (ref "ST_LINK") (pin "3") (pinfunction "3_3") (pintype "passive"))
    )
    (net (code "52") (name "USB+") (class "Default")
      (node (ref "D4") (pin "2") (pinfunction "2_2") (pintype "passive"))
      (node (ref "R13") (pin "1") (pinfunction "1_1") (pintype "passive"))
      (node (ref "R25") (pin "1") (pinfunction "1_1") (pintype "passive"))
      (node (ref "STM32") (pin "33") (pinfunction "PA12_33") (pintype "bidirectional"))
    )
    (net (code "53") (name "USB-") (class "Default")
      (node (ref "D3") (pin "2") (pinfunction "2_2") (pintype "passive"))
      (node (ref "R26") (pin "1") (pinfunction "1_1") (pintype "passive"))
      (node (ref "STM32") (pin "32") (pinfunction "PA11_32") (pintype "bidirectional"))
    )
    (net (code "54") (name "VBAT") (class "Default")
      (node (ref "BATTERIE") (pin "2") (pinfunction "S_2") (pintype "passive"))
      (node (ref "BATTERYCHARGER") (pin "3") (pinfunction "BAT_3") (pintype "bidirectional"))
      (node (ref "C4") (pin "+") (pinfunction "+_+") (pintype "passive"))
      (node (ref "H-BRUECKE") (pin "1") (pinfunction "VREF_1") (pintype "power_in"))
      (node (ref "H-BRUECKE") (pin "7") (pinfunction "VCC_7") (pintype "power_in"))
      (node (ref "Q3") (pin "2") (pinfunction "S_2") (pintype "passive"))
      (node (ref "R21") (pin "2") (pinfunction "2_2") (pintype "passive"))
    )
    (net (code "55") (name "VBUS") (class "Default")
      (node (ref "BATTERYCHARGER") (pin "4") (pinfunction "VCC_4") (pintype "bidirectional"))
      (node (ref "C12") (pin "1") (pinfunction "1_1") (pintype "passive"))
      (node (ref "D2") (pin "2") (pinfunction "2_2") (pintype "passive"))
      (node (ref "Q3") (pin "1") (pinfunction "G_1") (pintype "passive"))
      (node (ref "R11") (pin "2") (pinfunction "2_2") (pintype "passive"))
      (node (ref "R7") (pin "1") (pinfunction "1_1") (pintype "passive"))
      (node (ref "R8") (pin "1") (pinfunction "1_1") (pintype "passive"))
      (node (ref "SCHOTTKY1") (pin "A") (pinfunction "A_A") (pintype "passive"))
      (node (ref "USB-B") (pin "1") (pinfunction "VCC_1") (pintype "power_in"))
    )
    (net (code "56") (name "VIN") (class "Default")
      (node (ref "C16") (pin "1") (pinfunction "1_1") (pintype "passive"))
      (node (ref "L1") (pin "1") (pinfunction "1_1") (pintype "bidirectional"))
      (node (ref "Q3") (pin "3") (pinfunction "D_3") (pintype "passive"))
      (node (ref "SCHOTTKY1") (pin "C") (pinfunction "C_C") (pintype "passive"))
    )
    (net (code "57") (name "unconnected-(AUDIO_JACK-RING_2-Pad3)") (class "Default")
      (node (ref "AUDIO_JACK") (pin "3") (pinfunction "RING_2_3") (pintype "passive"))
    )
    (net (code "58") (name "unconnected-(AUDIO_JACK-TIP_1-Pad4)") (class "Default")
      (node (ref "AUDIO_JACK") (pin "4") (pinfunction "TIP_1_4") (pintype "passive"))
    )
    (net (code "59") (name "unconnected-(OPV-+IN1-Pad3)") (class "Default")
      (node (ref "OPV") (pin "3") (pinfunction "+IN1_3") (pintype "bidirectional"))
    )
    (net (code "60") (name "unconnected-(OPV-+IN2-Pad5)") (class "Default")
      (node (ref "OPV") (pin "5") (pinfunction "+IN2_5") (pintype "passive"))
    )
    (net (code "61") (name "unconnected-(OPV-+IN4-Pad12)") (class "Default")
      (node (ref "OPV") (pin "12") (pinfunction "+IN4_12") (pintype "bidirectional"))
    )
    (net (code "62") (name "unconnected-(OPV--IN1-Pad2)") (class "Default")
      (node (ref "OPV") (pin "2") (pinfunction "-IN1_2") (pintype "input"))
    )
    (net (code "63") (name "unconnected-(OPV--IN2-Pad6)") (class "Default")
      (node (ref "OPV") (pin "6") (pinfunction "-IN2_6") (pintype "passive"))
    )
    (net (code "64") (name "unconnected-(OPV--IN4-Pad13)") (class "Default")
      (node (ref "OPV") (pin "13") (pinfunction "-IN4_13") (pintype "bidirectional"))
    )
    (net (code "65") (name "unconnected-(OPV-OUT1-Pad1)") (class "Default")
      (node (ref "OPV") (pin "1") (pinfunction "OUT1_1") (pintype "input"))
    )
    (net (code "66") (name "unconnected-(OPV-OUT2-Pad7)") (class "Default")
      (node (ref "OPV") (pin "7") (pinfunction "OUT2_7") (pintype "passive"))
    )
    (net (code "67") (name "unconnected-(OPV-OUT4-Pad14)") (class "Default")
      (node (ref "OPV") (pin "14") (pinfunction "OUT4_14") (pintype "output"))
    )
    (net (code "68") (name "unconnected-(STM32-PA0_WKUP-Pad10)") (class "Default")
      (node (ref "STM32") (pin "10") (pinfunction "PA0_WKUP_10") (pintype "bidirectional"))
    )
    (net (code "69") (name "unconnected-(STM32-PA2-Pad12)") (class "Default")
      (node (ref "STM32") (pin "12") (pinfunction "PA2_12") (pintype "bidirectional"))
    )
    (net (code "70") (name "unconnected-(STM32-PA3-Pad13)") (class "Default")
      (node (ref "STM32") (pin "13") (pinfunction "PA3_13") (pintype "bidirectional"))
    )
    (net (code "71") (name "unconnected-(STM32-PA4-Pad14)") (class "Default")
      (node (ref "STM32") (pin "14") (pinfunction "PA4_14") (pintype "bidirectional"))
    )
    (net (code "72") (name "unconnected-(STM32-PA5-Pad15)") (class "Default")
      (node (ref "STM32") (pin "15") (pinfunction "PA5_15") (pintype "bidirectional"))
    )
    (net (code "73") (name "unconnected-(STM32-PA7-Pad17)") (class "Default")
      (node (ref "STM32") (pin "17") (pinfunction "PA7_17") (pintype "bidirectional"))
    )
    (net (code "74") (name "unconnected-(STM32-PA15-Pad38)") (class "Default")
      (node (ref "STM32") (pin "38") (pinfunction "PA15_38") (pintype "bidirectional"))
    )
    (net (code "75") (name "unconnected-(STM32-PB2-Pad20)") (class "Default")
      (node (ref "STM32") (pin "20") (pinfunction "PB2_20") (pintype "bidirectional"))
    )
    (net (code "76") (name "unconnected-(STM32-PB3-Pad39)") (class "Default")
      (node (ref "STM32") (pin "39") (pinfunction "PB3_39") (pintype "bidirectional"))
    )
    (net (code "77") (name "unconnected-(STM32-PB4-Pad40)") (class "Default")
      (node (ref "STM32") (pin "40") (pinfunction "PB4_40") (pintype "bidirectional"))
    )
    (net (code "78") (name "unconnected-(STM32-PB5-Pad41)") (class "Default")
      (node (ref "STM32") (pin "41") (pinfunction "PB5_41") (pintype "bidirectional"))
    )
    (net (code "79") (name "unconnected-(STM32-PB8-Pad45)") (class "Default")
      (node (ref "STM32") (pin "45") (pinfunction "PB8_45") (pintype "bidirectional"))
    )
    (net (code "80") (name "unconnected-(STM32-PB9-Pad46)") (class "Default")
      (node (ref "STM32") (pin "46") (pinfunction "PB9_46") (pintype "bidirectional"))
    )
    (net (code "81") (name "unconnected-(STM32-PB10-Pad21)") (class "Default")
      (node (ref "STM32") (pin "21") (pinfunction "PB10_21") (pintype "bidirectional"))
    )
    (net (code "82") (name "unconnected-(STM32-PB11-Pad22)") (class "Default")
      (node (ref "STM32") (pin "22") (pinfunction "PB11_22") (pintype "bidirectional"))
    )
    (net (code "83") (name "unconnected-(STM32-PB12-Pad25)") (class "Default")
      (node (ref "STM32") (pin "25") (pinfunction "PB12_25") (pintype "bidirectional"))
    )
  )
)
